# untitled.net
KiCad netlist of a schematic drawn in EAGLE
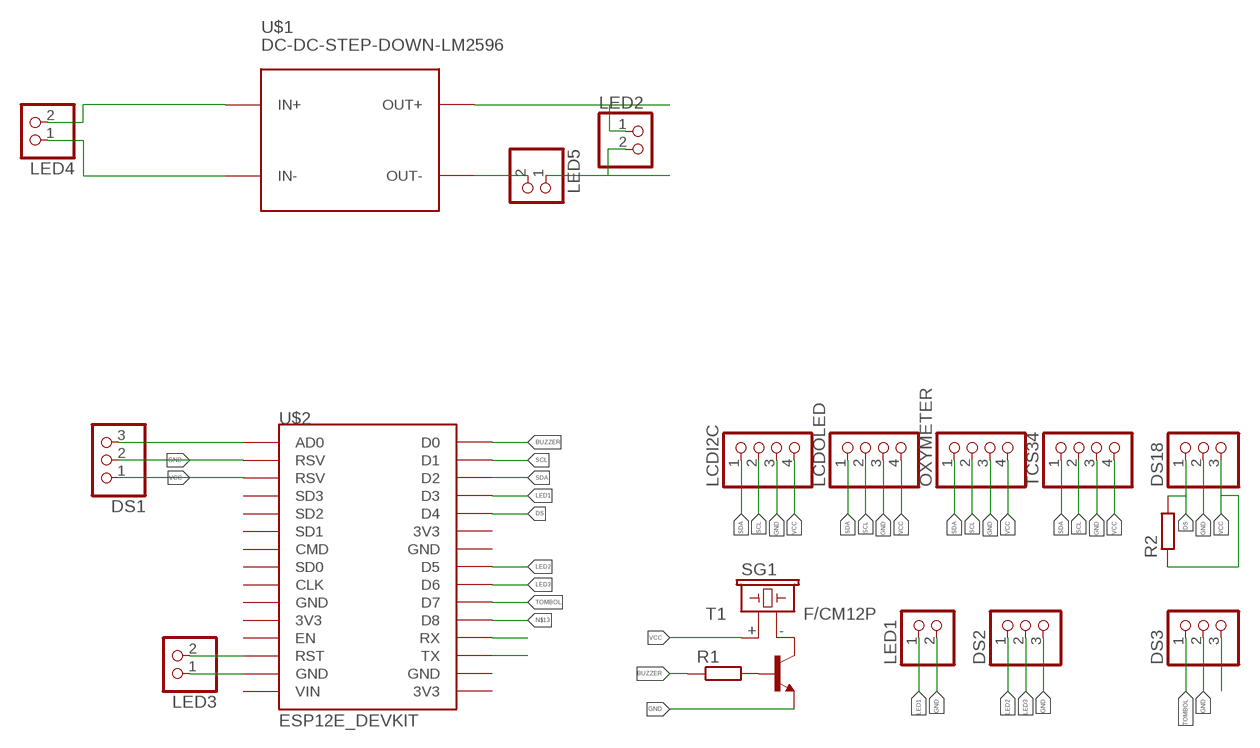
[diagram p0: schematic, sheet 1]

(export (version "E")
  (design (tool "Eeschema 10.0.6"))
  (components
    (comp (ref "DS1")
      (value "PINHD-1X3")
      (footprint "eagle-import:1X03")
      (libsource (lib "eagle-import") (part "PINHD-1X3"))
    )
    (comp (ref "DS2")
      (value "PINHD-1X3")
      (footprint "eagle-import:1X03")
      (libsource (lib "eagle-import") (part "PINHD-1X3"))
    )
    (comp (ref "DS3")
      (value "PINHD-1X3")
      (footprint "eagle-import:1X03")
      (libsource (lib "eagle-import") (part "PINHD-1X3"))
    )
    (comp (ref "DS18")
      (value "PINHD-1X3")
      (footprint "eagle-import:1X03")
      (libsource (lib "eagle-import") (part "PINHD-1X3"))
    )
    (comp (ref "LCDI2C")
      (value "PINHD-1X4")
      (footprint "eagle-import:1X04")
      (libsource (lib "eagle-import") (part "PINHD-1X4"))
    )
    (comp (ref "LCDOLED")
      (value "PINHD-1X4")
      (footprint "eagle-import:1X04")
      (libsource (lib "eagle-import") (part "PINHD-1X4"))
    )
    (comp (ref "LED1")
      (value "PINHD-1X2")
      (footprint "eagle-import:1X02")
      (libsource (lib "eagle-import") (part "PINHD-1X2"))
    )
    (comp (ref "LED2")
      (value "PINHD-1X2")
      (footprint "eagle-import:1X02")
      (libsource (lib "eagle-import") (part "PINHD-1X2"))
    )
    (comp (ref "LED3")
      (value "PINHD-1X2")
      (footprint "eagle-import:1X02")
      (libsource (lib "eagle-import") (part "PINHD-1X2"))
    )
    (comp (ref "LED4")
      (value "PINHD-1X2")
      (footprint "eagle-import:1X02")
      (libsource (lib "eagle-import") (part "PINHD-1X2"))
    )
    (comp (ref "LED5")
      (value "PINHD-1X2")
      (footprint "eagle-import:1X02")
      (libsource (lib "eagle-import") (part "PINHD-1X2"))
    )
    (comp (ref "OXYMETER")
      (value "PINHD-1X4")
      (footprint "eagle-import:1X04")
      (libsource (lib "eagle-import") (part "PINHD-1X4"))
    )
    (comp (ref "R1")
      (value "R-EU_0207/10")
      (footprint "eagle-import:0207_10")
      (libsource (lib "eagle-import") (part "R-EU_0207/10"))
    )
    (comp (ref "R2")
      (value "R-EU_0207/10")
      (footprint "eagle-import:0207_10")
      (libsource (lib "eagle-import") (part "R-EU_0207/10"))
    )
    (comp (ref "SG1")
      (value "F/CM12P")
      (footprint "eagle-import:F_CM12P")
      (libsource (lib "eagle-import") (part "F/CM12P"))
    )
    (comp (ref "T1")
      (value "-NPN-TO92")
      (footprint "eagle-import:TO92")
      (libsource (lib "eagle-import") (part "-NPN-TO92"))
    )
    (comp (ref "TCS34")
      (value "PINHD-1X4")
      (footprint "eagle-import:1X04")
      (libsource (lib "eagle-import") (part "PINHD-1X4"))
    )
    (comp (ref "U$1")
      (value "DC-DC-STEP-DOWN-LM2596")
      (footprint "eagle-import:DC-DC-STEP-DOWN-LM2596")
      (libsource (lib "eagle-import") (part "DC-DC-STEP-DOWN-LM2596"))
    )
    (comp (ref "U$2")
      (value "ESP12E_DEVKIT")
      (footprint "eagle-import:ESP12E_DEVKIT")
      (libsource (lib "eagle-import") (part "ESP12E_DEVKIT"))
    )
  )
  (nets
    (net (code "1") (name "BUZZER") (class "Default")
      (node (ref "R1") (pin "1") (pinfunction "1_1") (pintype "passive"))
      (node (ref "U$2") (pin "D0") (pinfunction "D0_D0") (pintype "bidirectional"))
    )
    (net (code "2") (name "DS") (class "Default")
      (node (ref "DS18") (pin "1") (pinfunction "1_1") (pintype "passive"))
      (node (ref "R2") (pin "2") (pinfunction "2_2") (pintype "passive"))
      (node (ref "U$2") (pin "D4") (pinfunction "D4_D4") (pintype "bidirectional"))
    )
    (net (code "3") (name "GND") (class "Default")
      (node (ref "DS1") (pin "2") (pinfunction "2_2") (pintype "passive"))
      (node (ref "DS18") (pin "2") (pinfunction "2_2") (pintype "passive"))
      (node (ref "DS2") (pin "3") (pinfunction "3_3") (pintype "passive"))
      (node (ref "DS3") (pin "2") (pinfunction "2_2") (pintype "passive"))
      (node (ref "LCDI2C") (pin "3") (pinfunction "3_3") (pintype "passive"))
      (node (ref "LCDOLED") (pin "3") (pinfunction "3_3") (pintype "passive"))
      (node (ref "LED1") (pin "2") (pinfunction "2_2") (pintype "passive"))
      (node (ref "LED2") (pin "2") (pinfunction "2_2") (pintype "passive"))
      (node (ref "LED5") (pin "1") (pinfunction "1_1") (pintype "passive"))
      (node (ref "OXYMETER") (pin "3") (pinfunction "3_3") (pintype "passive"))
      (node (ref "T1") (pin "1") (pinfunction "E_1") (pintype "passive"))
      (node (ref "TCS34") (pin "3") (pinfunction "3_3") (pintype "passive"))
      (node (ref "U$2") (pin "RSV@0") (pinfunction "RSV_RSV@0") (pintype "bidirectional"))
    )
    (net (code "4") (name "LED1") (class "Default")
      (node (ref "LED1") (pin "1") (pinfunction "1_1") (pintype "passive"))
      (node (ref "U$2") (pin "D3") (pinfunction "D3_D3") (pintype "bidirectional"))
    )
    (net (code "5") (name "LED2") (class "Default")
      (node (ref "DS2") (pin "1") (pinfunction "1_1") (pintype "passive"))
      (node (ref "U$2") (pin "D5") (pinfunction "D5_D5") (pintype "bidirectional"))
    )
    (net (code "6") (name "LED3") (class "Default")
      (node (ref "DS2") (pin "2") (pinfunction "2_2") (pintype "passive"))
      (node (ref "U$2") (pin "D6") (pinfunction "D6_D6") (pintype "bidirectional"))
    )
    (net (code "7") (name "N$13") (class "Default")
      (node (ref "U$2") (pin "D8") (pinfunction "D8_D8") (pintype "bidirectional"))
    )
    (net (code "8") (name "Net-(DS1-Pad3)") (class "Default")
      (node (ref "DS1") (pin "3") (pinfunction "3_3") (pintype "passive"))
      (node (ref "U$2") (pin "AD0") (pinfunction "AD0_AD0") (pintype "bidirectional"))
    )
    (net (code "9") (name "Net-(LED3-Pad1)") (class "Default")
      (node (ref "LED3") (pin "1") (pinfunction "1_1") (pintype "passive"))
      (node (ref "U$2") (pin "GND@1") (pinfunction "GND_GND@1") (pintype "bidirectional"))
    )
    (net (code "10") (name "Net-(LED3-Pad2)") (class "Default")
      (node (ref "LED3") (pin "2") (pinfunction "2_2") (pintype "passive"))
      (node (ref "U$2") (pin "RST") (pinfunction "RST_RST") (pintype "bidirectional"))
    )
    (net (code "11") (name "Net-(LED4-Pad1)") (class "Default")
      (node (ref "LED4") (pin "1") (pinfunction "1_1") (pintype "passive"))
      (node (ref "U$1") (pin "IN-") (pinfunction "IN-_IN-") (pintype "bidirectional"))
    )
    (net (code "12") (name "Net-(LED4-Pad2)") (class "Default")
      (node (ref "LED4") (pin "2") (pinfunction "2_2") (pintype "passive"))
      (node (ref "U$1") (pin "IN+") (pinfunction "IN+_IN+") (pintype "bidirectional"))
    )
    (net (code "13") (name "Net-(LED5-Pad2)") (class "Default")
      (node (ref "LED5") (pin "2") (pinfunction "2_2") (pintype "passive"))
      (node (ref "U$1") (pin "OUT-") (pinfunction "OUT-_OUT-") (pintype "bidirectional"))
    )
    (net (code "14") (name "Net-(SG1-2)") (class "Default")
      (node (ref "SG1") (pin "-") (pinfunction "2_-") (pintype "passive"))
      (node (ref "T1") (pin "3") (pinfunction "C_3") (pintype "passive"))
    )
    (net (code "15") (name "Net-(T1-B)") (class "Default")
      (node (ref "R1") (pin "2") (pinfunction "2_2") (pintype "passive"))
      (node (ref "T1") (pin "2") (pinfunction "B_2") (pintype "passive"))
    )
    (net (code "16") (name "SCL") (class "Default")
      (node (ref "LCDI2C") (pin "2") (pinfunction "2_2") (pintype "passive"))
      (node (ref "LCDOLED") (pin "2") (pinfunction "2_2") (pintype "passive"))
      (node (ref "OXYMETER") (pin "2") (pinfunction "2_2") (pintype "passive"))
      (node (ref "TCS34") (pin "2") (pinfunction "2_2") (pintype "passive"))
      (node (ref "U$2") (pin "D1") (pinfunction "D1_D1") (pintype "bidirectional"))
    )
    (net (code "17") (name "SDA") (class "Default")
      (node (ref "LCDI2C") (pin "1") (pinfunction "1_1") (pintype "passive"))
      (node (ref "LCDOLED") (pin "1") (pinfunction "1_1") (pintype "passive"))
      (node (ref "OXYMETER") (pin "1") (pinfunction "1_1") (pintype "passive"))
      (node (ref "TCS34") (pin "1") (pinfunction "1_1") (pintype "passive"))
      (node (ref "U$2") (pin "D2") (pinfunction "D2_D2") (pintype "bidirectional"))
    )
    (net (code "18") (name "TOMBOL") (class "Default")
      (node (ref "DS3") (pin "1") (pinfunction "1_1") (pintype "passive"))
      (node (ref "U$2") (pin "D7") (pinfunction "D7_D7") (pintype "bidirectional"))
    )
    (net (code "19") (name "VCC") (class "Default")
      (node (ref "DS1") (pin "1") (pinfunction "1_1") (pintype "passive"))
      (node (ref "DS18") (pin "3") (pinfunction "3_3") (pintype "passive"))
      (node (ref "DS3") (pin "3") (pinfunction "3_3") (pintype "passive"))
      (node (ref "LCDI2C") (pin "4") (pinfunction "4_4") (pintype "passive"))
      (node (ref "LCDOLED") (pin "4") (pinfunction "4_4") (pintype "passive"))
      (node (ref "LED2") (pin "1") (pinfunction "1_1") (pintype "passive"))
      (node (ref "OXYMETER") (pin "4") (pinfunction "4_4") (pintype "passive"))
      (node (ref "R2") (pin "1") (pinfunction "1_1") (pintype "passive"))
      (node (ref "SG1") (pin "+") (pinfunction "1_+") (pintype "passive"))
      (node (ref "TCS34") (pin "4") (pinfunction "4_4") (pintype "passive"))
      (node (ref "U$1") (pin "OUT+") (pinfunction "OUT+_OUT+") (pintype "bidirectional"))
      (node (ref "U$2") (pin "RSV@1") (pinfunction "RSV_RSV@1") (pintype "bidirectional"))
    )
    (net (code "20") (name "unconnected-(U$2-3V3-Pad3V3@0)") (class "Default")
      (node (ref "U$2") (pin "3V3@0") (pinfunction "3V3_3V3@0") (pintype "bidirectional"))
    )
    (net (code "21") (name "unconnected-(U$2-3V3-Pad3V3@1)") (class "Default")
      (node (ref "U$2") (pin "3V3@1") (pinfunction "3V3_3V3@1") (pintype "bidirectional"))
    )
    (net (code "22") (name "unconnected-(U$2-3V3-Pad3V3@2)") (class "Default")
      (node (ref "U$2") (pin "3V3@2") (pinfunction "3V3_3V3@2") (pintype "bidirectional"))
    )
    (net (code "23") (name "unconnected-(U$2-GND-PadGND@0)") (class "Default")
      (node (ref "U$2") (pin "GND@0") (pinfunction "GND_GND@0") (pintype "bidirectional"))
    )
    (net (code "24") (name "unconnected-(U$2-GND-PadGND@2)") (class "Default")
      (node (ref "U$2") (pin "GND@2") (pinfunction "GND_GND@2") (pintype "bidirectional"))
    )
    (net (code "25") (name "unconnected-(U$2-GND-PadGND@3)") (class "Default")
      (node (ref "U$2") (pin "GND@3") (pinfunction "GND_GND@3") (pintype "bidirectional"))
    )
    (net (code "26") (name "unconnected-(U$2-PadCLK)") (class "Default")
      (node (ref "U$2") (pin "CLK") (pinfunction "CLK_CLK") (pintype "bidirectional"))
    )
    (net (code "27") (name "unconnected-(U$2-PadCMD)") (class "Default")
      (node (ref "U$2") (pin "CMD") (pinfunction "CMD_CMD") (pintype "bidirectional"))
    )
    (net (code "28") (name "unconnected-(U$2-PadEN)") (class "Default")
      (node (ref "U$2") (pin "EN") (pinfunction "EN_EN") (pintype "bidirectional"))
    )
    (net (code "29") (name "unconnected-(U$2-PadRX)") (class "Default")
      (node (ref "U$2") (pin "RX") (pinfunction "RX_RX") (pintype "bidirectional"))
    )
    (net (code "30") (name "unconnected-(U$2-PadSD0)") (class "Default")
      (node (ref "U$2") (pin "SD0") (pinfunction "SD0_SD0") (pintype "bidirectional"))
    )
    (net (code "31") (name "unconnected-(U$2-PadSD1)") (class "Default")
      (node (ref "U$2") (pin "SD1") (pinfunction "SD1_SD1") (pintype "bidirectional"))
    )
    (net (code "32") (name "unconnected-(U$2-PadSD2)") (class "Default")
      (node (ref "U$2") (pin "SD2") (pinfunction "SD2_SD2") (pintype "bidirectional"))
    )
    (net (code "33") (name "unconnected-(U$2-PadSD3)") (class "Default")
      (node (ref "U$2") (pin "SD3") (pinfunction "SD3_SD3") (pintype "bidirectional"))
    )
    (net (code "34") (name "unconnected-(U$2-PadTX)") (class "Default")
      (node (ref "U$2") (pin "TX") (pinfunction "TX_TX") (pintype "bidirectional"))
    )
    (net (code "35") (name "unconnected-(U$2-PadVIN)") (class "Default")
      (node (ref "U$2") (pin "VIN") (pinfunction "VIN_VIN") (pintype "bidirectional"))
    )
  )
)
